# Fuentes.net
KiCad netlist of a schematic drawn in Altium Designer
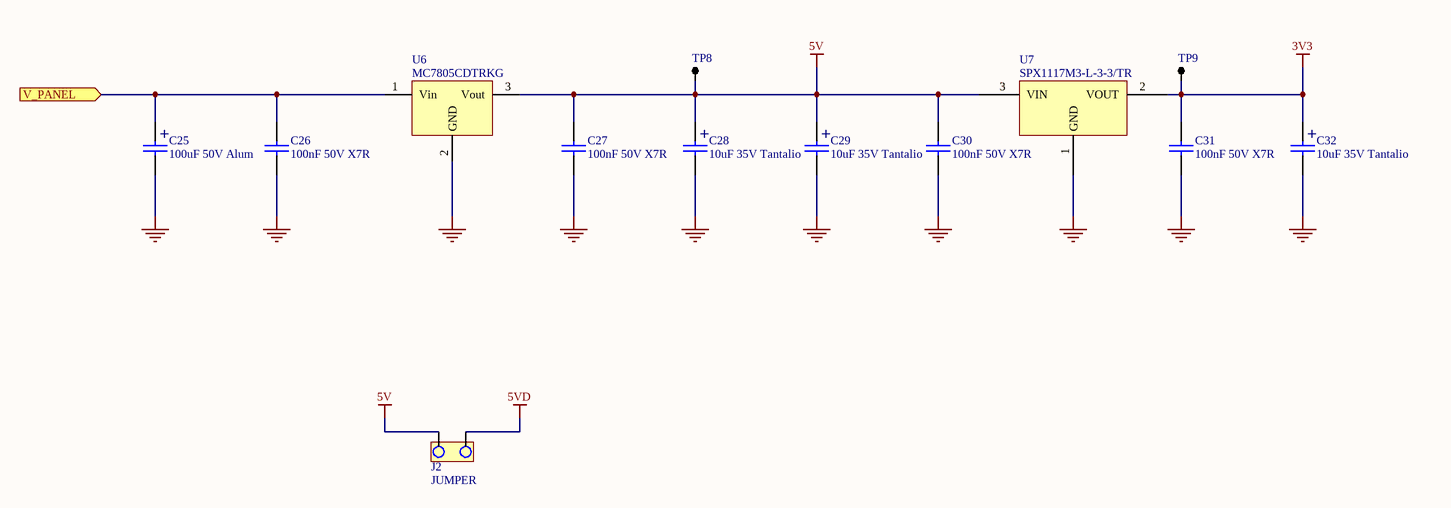
[diagram p0: Fuentes.SchDoc]

(export (version "E")
  (design (tool "Eeschema 10.0.6"))
  (components
    (comp (ref "C25")
      (value "100uF 50V Alum")
      (footprint "CAPSMD8x8.3")
      (description "UWZ1H101MCL1GS")
      (libsource (lib "Libreria_Casera") (part "CAPPOL"))
    )
    (comp (ref "C26")
      (value "100nF 50V X7R")
      (footprint "0805")
      (libsource (lib "Libreria_Casera") (part "CAP"))
    )
    (comp (ref "C27")
      (value "100nF 50V X7R")
      (footprint "0805")
      (libsource (lib "Libreria_Casera") (part "CAP"))
    )
    (comp (ref "C28")
      (value "10uF 35V Tantalio")
      (footprint "CAPPOL1210")
      (description "TCJB106M035R0200")
      (libsource (lib "Libreria_Casera") (part "CAPPOL"))
    )
    (comp (ref "C29")
      (value "10uF 35V Tantalio")
      (footprint "CAPPOL1210")
      (description "TCJB106M035R0200")
      (libsource (lib "Libreria_Casera") (part "CAPPOL"))
    )
    (comp (ref "C30")
      (value "100nF 50V X7R")
      (footprint "0805")
      (libsource (lib "Libreria_Casera") (part "CAP"))
    )
    (comp (ref "C31")
      (value "100nF 50V X7R")
      (footprint "0805")
      (libsource (lib "Libreria_Casera") (part "CAP"))
    )
    (comp (ref "C32")
      (value "10uF 35V Tantalio")
      (footprint "CAPPOL1210")
      (description "TCJB106M035R0200")
      (libsource (lib "Libreria_Casera") (part "CAPPOL"))
    )
    (comp (ref "J2") (value "JUMPER") (footprint "0805") (libsource (lib "Libreria_Casera") (part "JUMPER")))
    (comp (ref "TP8") (value "TP") (footprint "TP_COMPACT") (libsource (lib "Libreria_Casera") (part "TP")))
    (comp (ref "TP9") (value "TP") (footprint "TP_COMPACT") (libsource (lib "Libreria_Casera") (part "TP")))
    (comp (ref "U6") (value "MC7805CDTRKG") (footprint "dpak") (libsource (lib "MPPTLib") (part "LM78XX")))
    (comp (ref "U7")
      (value "SPX1117M3-L-3-3/TR")
      (footprint "SOT223")
      (libsource (lib "MPPTLib") (part "LIN_REG"))
    )
  )
  (nets
    (net (code "1") (name "/V_PANEL") (class "Default")
      (node (ref "C25") (pin "1") (pinfunction "1_1") (pintype "passive"))
      (node (ref "C26") (pin "1") (pinfunction "1_1") (pintype "passive"))
      (node (ref "U6") (pin "1") (pinfunction "Vin_1") (pintype "passive"))
    )
    (net (code "2") (name "3V3") (class "Default")
      (node (ref "C31") (pin "1") (pinfunction "1_1") (pintype "passive"))
      (node (ref "C32") (pin "1") (pinfunction "1_1") (pintype "passive"))
      (node (ref "TP9") (pin "1") (pinfunction "1_1") (pintype "passive"))
      (node (ref "U7") (pin "2") (pinfunction "VOUT_2") (pintype "passive"))
    )
    (net (code "3") (name "5V") (class "Default")
      (node (ref "C27") (pin "1") (pinfunction "1_1") (pintype "passive"))
      (node (ref "C28") (pin "1") (pinfunction "1_1") (pintype "passive"))
      (node (ref "C29") (pin "1") (pinfunction "1_1") (pintype "passive"))
      (node (ref "C30") (pin "2") (pinfunction "2_2") (pintype "passive"))
      (node (ref "J2") (pin "1") (pinfunction "1_1") (pintype "passive"))
      (node (ref "TP8") (pin "1") (pinfunction "1_1") (pintype "passive"))
      (node (ref "U6") (pin "3") (pinfunction "Vout_3") (pintype "passive"))
      (node (ref "U7") (pin "3") (pinfunction "VIN_3") (pintype "passive"))
    )
    (net (code "4") (name "5VD") (class "Default")
      (node (ref "J2") (pin "2") (pinfunction "2_2") (pintype "passive"))
    )
    (net (code "5") (name "GND") (class "Default")
      (node (ref "C25") (pin "2") (pinfunction "2_2") (pintype "passive"))
      (node (ref "C26") (pin "2") (pinfunction "2_2") (pintype "passive"))
      (node (ref "C27") (pin "2") (pinfunction "2_2") (pintype "passive"))
      (node (ref "C28") (pin "2") (pinfunction "2_2") (pintype "passive"))
      (node (ref "C29") (pin "2") (pinfunction "2_2") (pintype "passive"))
      (node (ref "C30") (pin "1") (pinfunction "1_1") (pintype "passive"))
      (node (ref "C31") (pin "2") (pinfunction "2_2") (pintype "passive"))
      (node (ref "C32") (pin "2") (pinfunction "2_2") (pintype "passive"))
      (node (ref "U6") (pin "2") (pinfunction "GND_2") (pintype "passive"))
      (node (ref "U7") (pin "1") (pinfunction "GND_1") (pintype "passive"))
    )
  )
)
